# receiver.net
KiCad netlist of a schematic drawn in EAGLE
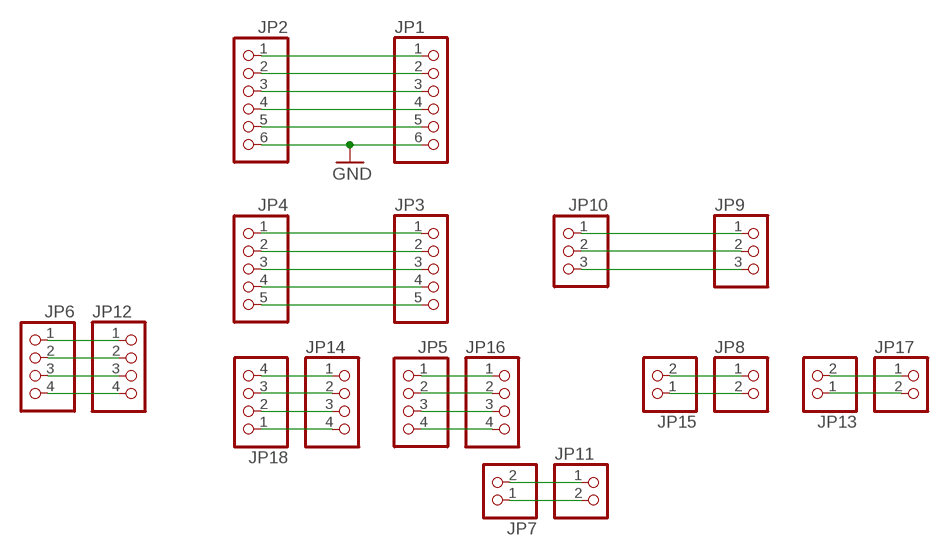
[diagram p0: schematic, sheet 1]

(export (version "E")
  (design (tool "Eeschema 10.0.6"))
  (components
    (comp (ref "JP1")
      (value "PINHD-1X6")
      (footprint "eagle-import:1X06")
      (libsource (lib "eagle-import") (part "PINHD-1X6"))
    )
    (comp (ref "JP2")
      (value "PINHD-1X6")
      (footprint "eagle-import:1X06")
      (libsource (lib "eagle-import") (part "PINHD-1X6"))
    )
    (comp (ref "JP3")
      (value "PINHD-1X5")
      (footprint "eagle-import:1X05")
      (libsource (lib "eagle-import") (part "PINHD-1X5"))
    )
    (comp (ref "JP4")
      (value "PINHD-1X5")
      (footprint "eagle-import:1X05")
      (libsource (lib "eagle-import") (part "PINHD-1X5"))
    )
    (comp (ref "JP5")
      (value "PINHD-1X4")
      (footprint "eagle-import:1X04")
      (libsource (lib "eagle-import") (part "PINHD-1X4"))
    )
    (comp (ref "JP6")
      (value "PINHD-1X4")
      (footprint "eagle-import:1X04")
      (libsource (lib "eagle-import") (part "PINHD-1X4"))
    )
    (comp (ref "JP7")
      (value "PINHD-1X2")
      (footprint "eagle-import:1X02")
      (libsource (lib "eagle-import") (part "PINHD-1X2"))
    )
    (comp (ref "JP8")
      (value "PINHD-1X2")
      (footprint "eagle-import:1X02")
      (libsource (lib "eagle-import") (part "PINHD-1X2"))
    )
    (comp (ref "JP9")
      (value "PINHD-1X3")
      (footprint "eagle-import:1X03")
      (libsource (lib "eagle-import") (part "PINHD-1X3"))
    )
    (comp (ref "JP10")
      (value "PINHD-1X3")
      (footprint "eagle-import:1X03")
      (libsource (lib "eagle-import") (part "PINHD-1X3"))
    )
    (comp (ref "JP11")
      (value "PINHD-1X2")
      (footprint "eagle-import:1X02")
      (libsource (lib "eagle-import") (part "PINHD-1X2"))
    )
    (comp (ref "JP12")
      (value "PINHD-1X4")
      (footprint "eagle-import:1X04")
      (libsource (lib "eagle-import") (part "PINHD-1X4"))
    )
    (comp (ref "JP13")
      (value "PINHD-1X2")
      (footprint "eagle-import:1X02")
      (libsource (lib "eagle-import") (part "PINHD-1X2"))
    )
    (comp (ref "JP14")
      (value "PINHD-1X4")
      (footprint "eagle-import:1X04")
      (libsource (lib "eagle-import") (part "PINHD-1X4"))
    )
    (comp (ref "JP15")
      (value "PINHD-1X2")
      (footprint "eagle-import:1X02")
      (libsource (lib "eagle-import") (part "PINHD-1X2"))
    )
    (comp (ref "JP16")
      (value "PINHD-1X4")
      (footprint "eagle-import:1X04")
      (libsource (lib "eagle-import") (part "PINHD-1X4"))
    )
    (comp (ref "JP17")
      (value "PINHD-1X2")
      (footprint "eagle-import:1X02")
      (libsource (lib "eagle-import") (part "PINHD-1X2"))
    )
    (comp (ref "JP18")
      (value "PINHD-1X4")
      (footprint "eagle-import:1X04")
      (libsource (lib "eagle-import") (part "PINHD-1X4"))
    )
  )
  (nets
    (net (code "1") (name "GND") (class "Default")
      (node (ref "JP1") (pin "6") (pinfunction "6_6") (pintype "passive"))
      (node (ref "JP2") (pin "6") (pinfunction "6_6") (pintype "passive"))
    )
    (net (code "2") (name "Net-(JP1-Pad1)") (class "Default")
      (node (ref "JP1") (pin "1") (pinfunction "1_1") (pintype "passive"))
      (node (ref "JP2") (pin "1") (pinfunction "1_1") (pintype "passive"))
    )
    (net (code "3") (name "Net-(JP1-Pad2)") (class "Default")
      (node (ref "JP1") (pin "2") (pinfunction "2_2") (pintype "passive"))
      (node (ref "JP2") (pin "2") (pinfunction "2_2") (pintype "passive"))
    )
    (net (code "4") (name "Net-(JP1-Pad3)") (class "Default")
      (node (ref "JP1") (pin "3") (pinfunction "3_3") (pintype "passive"))
      (node (ref "JP2") (pin "3") (pinfunction "3_3") (pintype "passive"))
    )
    (net (code "5") (name "Net-(JP1-Pad4)") (class "Default")
      (node (ref "JP1") (pin "4") (pinfunction "4_4") (pintype "passive"))
      (node (ref "JP2") (pin "4") (pinfunction "4_4") (pintype "passive"))
    )
    (net (code "6") (name "Net-(JP1-Pad5)") (class "Default")
      (node (ref "JP1") (pin "5") (pinfunction "5_5") (pintype "passive"))
      (node (ref "JP2") (pin "5") (pinfunction "5_5") (pintype "passive"))
    )
    (net (code "7") (name "Net-(JP3-Pad1)") (class "Default")
      (node (ref "JP3") (pin "1") (pinfunction "1_1") (pintype "passive"))
      (node (ref "JP4") (pin "1") (pinfunction "1_1") (pintype "passive"))
    )
    (net (code "8") (name "Net-(JP3-Pad2)") (class "Default")
      (node (ref "JP3") (pin "2") (pinfunction "2_2") (pintype "passive"))
      (node (ref "JP4") (pin "2") (pinfunction "2_2") (pintype "passive"))
    )
    (net (code "9") (name "Net-(JP3-Pad3)") (class "Default")
      (node (ref "JP3") (pin "3") (pinfunction "3_3") (pintype "passive"))
      (node (ref "JP4") (pin "3") (pinfunction "3_3") (pintype "passive"))
    )
    (net (code "10") (name "Net-(JP3-Pad4)") (class "Default")
      (node (ref "JP3") (pin "4") (pinfunction "4_4") (pintype "passive"))
      (node (ref "JP4") (pin "4") (pinfunction "4_4") (pintype "passive"))
    )
    (net (code "11") (name "Net-(JP3-Pad5)") (class "Default")
      (node (ref "JP3") (pin "5") (pinfunction "5_5") (pintype "passive"))
      (node (ref "JP4") (pin "5") (pinfunction "5_5") (pintype "passive"))
    )
    (net (code "12") (name "Net-(JP10-Pad1)") (class "Default")
      (node (ref "JP10") (pin "1") (pinfunction "1_1") (pintype "passive"))
      (node (ref "JP9") (pin "1") (pinfunction "1_1") (pintype "passive"))
    )
    (net (code "13") (name "Net-(JP10-Pad2)") (class "Default")
      (node (ref "JP10") (pin "2") (pinfunction "2_2") (pintype "passive"))
      (node (ref "JP9") (pin "2") (pinfunction "2_2") (pintype "passive"))
    )
    (net (code "14") (name "Net-(JP10-Pad3)") (class "Default")
      (node (ref "JP10") (pin "3") (pinfunction "3_3") (pintype "passive"))
      (node (ref "JP9") (pin "3") (pinfunction "3_3") (pintype "passive"))
    )
    (net (code "15") (name "Net-(JP11-Pad1)") (class "Default")
      (node (ref "JP11") (pin "1") (pinfunction "1_1") (pintype "passive"))
      (node (ref "JP7") (pin "2") (pinfunction "2_2") (pintype "passive"))
    )
    (net (code "16") (name "Net-(JP11-Pad2)") (class "Default")
      (node (ref "JP11") (pin "2") (pinfunction "2_2") (pintype "passive"))
      (node (ref "JP7") (pin "1") (pinfunction "1_1") (pintype "passive"))
    )
    (net (code "17") (name "Net-(JP12-Pad1)") (class "Default")
      (node (ref "JP12") (pin "1") (pinfunction "1_1") (pintype "passive"))
      (node (ref "JP6") (pin "1") (pinfunction "1_1") (pintype "passive"))
    )
    (net (code "18") (name "Net-(JP12-Pad2)") (class "Default")
      (node (ref "JP12") (pin "2") (pinfunction "2_2") (pintype "passive"))
      (node (ref "JP6") (pin "2") (pinfunction "2_2") (pintype "passive"))
    )
    (net (code "19") (name "Net-(JP12-Pad3)") (class "Default")
      (node (ref "JP12") (pin "3") (pinfunction "3_3") (pintype "passive"))
      (node (ref "JP6") (pin "3") (pinfunction "3_3") (pintype "passive"))
    )
    (net (code "20") (name "Net-(JP12-Pad4)") (class "Default")
      (node (ref "JP12") (pin "4") (pinfunction "4_4") (pintype "passive"))
      (node (ref "JP6") (pin "4") (pinfunction "4_4") (pintype "passive"))
    )
    (net (code "21") (name "Net-(JP13-Pad1)") (class "Default")
      (node (ref "JP13") (pin "1") (pinfunction "1_1") (pintype "passive"))
      (node (ref "JP17") (pin "2") (pinfunction "2_2") (pintype "passive"))
    )
    (net (code "22") (name "Net-(JP13-Pad2)") (class "Default")
      (node (ref "JP13") (pin "2") (pinfunction "2_2") (pintype "passive"))
      (node (ref "JP17") (pin "1") (pinfunction "1_1") (pintype "passive"))
    )
    (net (code "23") (name "Net-(JP14-Pad1)") (class "Default")
      (node (ref "JP14") (pin "1") (pinfunction "1_1") (pintype "passive"))
      (node (ref "JP18") (pin "4") (pinfunction "4_4") (pintype "passive"))
    )
    (net (code "24") (name "Net-(JP14-Pad2)") (class "Default")
      (node (ref "JP14") (pin "2") (pinfunction "2_2") (pintype "passive"))
      (node (ref "JP18") (pin "3") (pinfunction "3_3") (pintype "passive"))
    )
    (net (code "25") (name "Net-(JP14-Pad3)") (class "Default")
      (node (ref "JP14") (pin "3") (pinfunction "3_3") (pintype "passive"))
      (node (ref "JP18") (pin "2") (pinfunction "2_2") (pintype "passive"))
    )
    (net (code "26") (name "Net-(JP14-Pad4)") (class "Default")
      (node (ref "JP14") (pin "4") (pinfunction "4_4") (pintype "passive"))
      (node (ref "JP18") (pin "1") (pinfunction "1_1") (pintype "passive"))
    )
    (net (code "27") (name "Net-(JP15-Pad1)") (class "Default")
      (node (ref "JP15") (pin "1") (pinfunction "1_1") (pintype "passive"))
      (node (ref "JP8") (pin "2") (pinfunction "2_2") (pintype "passive"))
    )
    (net (code "28") (name "Net-(JP15-Pad2)") (class "Default")
      (node (ref "JP15") (pin "2") (pinfunction "2_2") (pintype "passive"))
      (node (ref "JP8") (pin "1") (pinfunction "1_1") (pintype "passive"))
    )
    (net (code "29") (name "Net-(JP16-Pad1)") (class "Default")
      (node (ref "JP16") (pin "1") (pinfunction "1_1") (pintype "passive"))
      (node (ref "JP5") (pin "1") (pinfunction "1_1") (pintype "passive"))
    )
    (net (code "30") (name "Net-(JP16-Pad2)") (class "Default")
      (node (ref "JP16") (pin "2") (pinfunction "2_2") (pintype "passive"))
      (node (ref "JP5") (pin "2") (pinfunction "2_2") (pintype "passive"))
    )
    (net (code "31") (name "Net-(JP16-Pad3)") (class "Default")
      (node (ref "JP16") (pin "3") (pinfunction "3_3") (pintype "passive"))
      (node (ref "JP5") (pin "3") (pinfunction "3_3") (pintype "passive"))
    )
    (net (code "32") (name "Net-(JP16-Pad4)") (class "Default")
      (node (ref "JP16") (pin "4") (pinfunction "4_4") (pintype "passive"))
      (node (ref "JP5") (pin "4") (pinfunction "4_4") (pintype "passive"))
    )
  )
)
